# FULL_CB_80_Pin_REV_D.net
KiCad netlist of a schematic drawn in Altium Designer
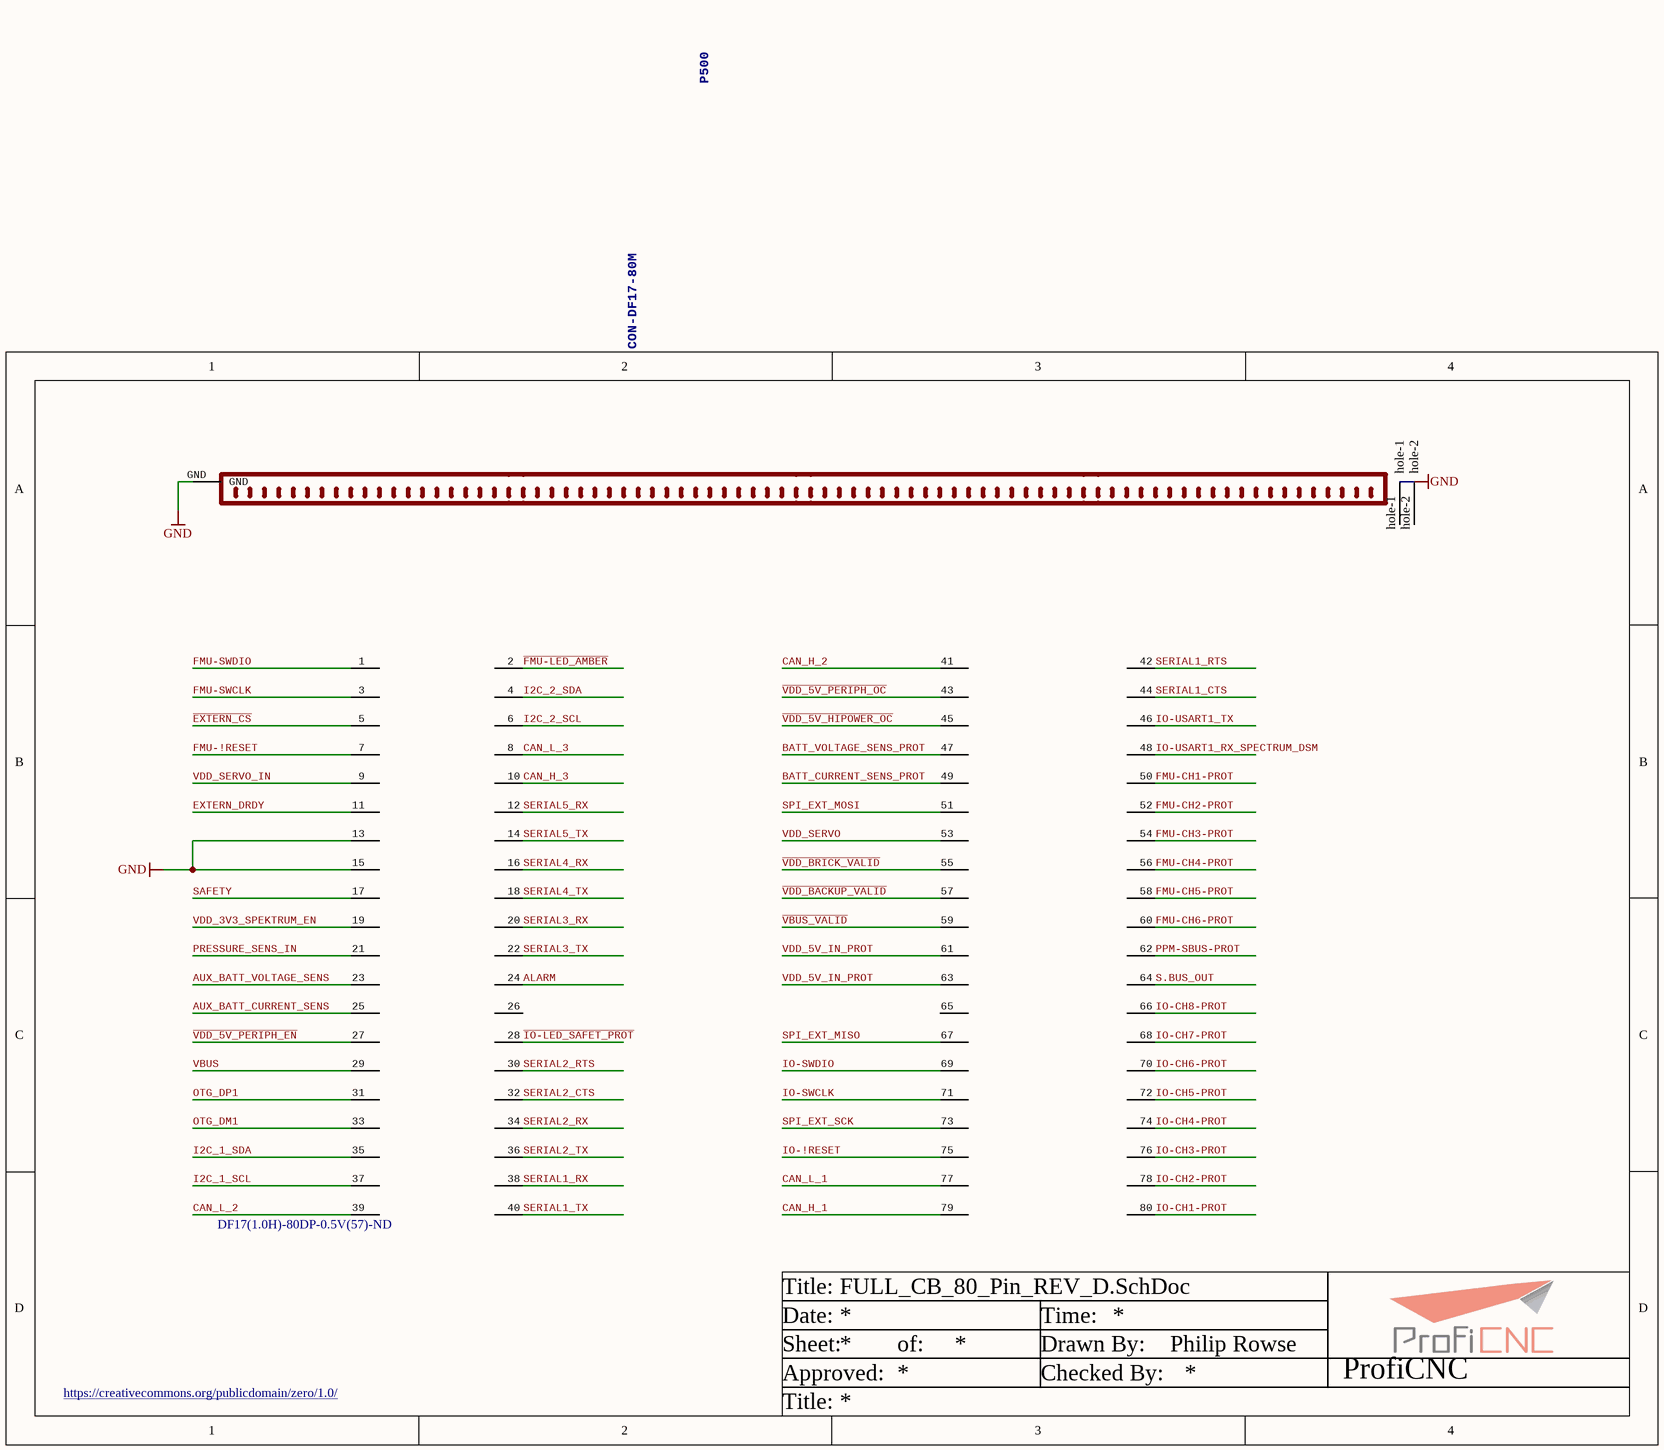
[diagram p0: FULL_CB_80_Pin_REV_D.SchDoc]

(export (version "E")
  (design (tool "Eeschema 10.0.6"))
  (components
    (comp (ref "P500")
      (value "CON-DF17-80M")
      (description "Connector, Header, 80Pos, .5MM, DUAL, SMD, Au")
      (fields (field (name "SUPPLIER PART NUMBER 1") "DF17(1.0H)-80DP-0.5V(57)-ND"))
      (libsource (lib "CB_REV_C") (part "CON-DF17-80M"))
    )
  )
  (nets
    (net (code "1") (name "/ALARM") (class "Default")
      (node (ref "P500") (pin "24") (pinfunction "24_24") (pintype "passive"))
    )
    (net (code "2") (name "/AUX_BATT_CURRENT_SENS") (class "Default")
      (node (ref "P500") (pin "25") (pinfunction "25_25") (pintype "passive"))
    )
    (net (code "3") (name "/AUX_BATT_VOLTAGE_SENS") (class "Default")
      (node (ref "P500") (pin "23") (pinfunction "23_23") (pintype "passive"))
    )
    (net (code "4") (name "/BATT_CURRENT_SENS_PROT") (class "Default")
      (node (ref "P500") (pin "49") (pinfunction "49_49") (pintype "passive"))
    )
    (net (code "5") (name "/BATT_VOLTAGE_SENS_PROT") (class "Default")
      (node (ref "P500") (pin "47") (pinfunction "47_47") (pintype "passive"))
    )
    (net (code "6") (name "/CAN_H_1") (class "Default")
      (node (ref "P500") (pin "79") (pinfunction "79_79") (pintype "passive"))
    )
    (net (code "7") (name "/CAN_H_2") (class "Default")
      (node (ref "P500") (pin "41") (pinfunction "41_41") (pintype "passive"))
    )
    (net (code "8") (name "/CAN_H_3") (class "Default")
      (node (ref "P500") (pin "10") (pinfunction "10_10") (pintype "passive"))
    )
    (net (code "9") (name "/CAN_L_1") (class "Default")
      (node (ref "P500") (pin "77") (pinfunction "77_77") (pintype "passive"))
    )
    (net (code "10") (name "/CAN_L_2") (class "Default")
      (node (ref "P500") (pin "39") (pinfunction "39_39") (pintype "passive"))
    )
    (net (code "11") (name "/CAN_L_3") (class "Default")
      (node (ref "P500") (pin "8") (pinfunction "8_8") (pintype "passive"))
    )
    (net (code "12") (name "/EXTERN_DRDY") (class "Default")
      (node (ref "P500") (pin "11") (pinfunction "11_11") (pintype "passive"))
    )
    (net (code "13") (name "/FMU-!RESET") (class "Default")
      (node (ref "P500") (pin "7") (pinfunction "7_7") (pintype "passive"))
    )
    (net (code "14") (name "/FMU-CH1-PROT") (class "Default")
      (node (ref "P500") (pin "50") (pinfunction "50_50") (pintype "passive"))
    )
    (net (code "15") (name "/FMU-CH2-PROT") (class "Default")
      (node (ref "P500") (pin "52") (pinfunction "52_52") (pintype "passive"))
    )
    (net (code "16") (name "/FMU-CH3-PROT") (class "Default")
      (node (ref "P500") (pin "54") (pinfunction "54_54") (pintype "passive"))
    )
    (net (code "17") (name "/FMU-CH4-PROT") (class "Default")
      (node (ref "P500") (pin "56") (pinfunction "56_56") (pintype "passive"))
    )
    (net (code "18") (name "/FMU-CH5-PROT") (class "Default")
      (node (ref "P500") (pin "58") (pinfunction "58_58") (pintype "passive"))
    )
    (net (code "19") (name "/FMU-CH6-PROT") (class "Default")
      (node (ref "P500") (pin "60") (pinfunction "60_60") (pintype "passive"))
    )
    (net (code "20") (name "/FMU-SWCLK") (class "Default")
      (node (ref "P500") (pin "3") (pinfunction "3_3") (pintype "passive"))
    )
    (net (code "21") (name "/FMU-SWDIO") (class "Default")
      (node (ref "P500") (pin "1") (pinfunction "1_1") (pintype "passive"))
    )
    (net (code "22") (name "/I2C_1_SCL") (class "Default")
      (node (ref "P500") (pin "37") (pinfunction "37_37") (pintype "passive"))
    )
    (net (code "23") (name "/I2C_1_SDA") (class "Default")
      (node (ref "P500") (pin "35") (pinfunction "35_35") (pintype "passive"))
    )
    (net (code "24") (name "/I2C_2_SCL") (class "Default")
      (node (ref "P500") (pin "6") (pinfunction "6_6") (pintype "passive"))
    )
    (net (code "25") (name "/I2C_2_SDA") (class "Default")
      (node (ref "P500") (pin "4") (pinfunction "4_4") (pintype "passive"))
    )
    (net (code "26") (name "/IO-!RESET") (class "Default")
      (node (ref "P500") (pin "75") (pinfunction "75_75") (pintype "passive"))
    )
    (net (code "27") (name "/IO-CH1-PROT") (class "Default")
      (node (ref "P500") (pin "80") (pinfunction "80_80") (pintype "passive"))
    )
    (net (code "28") (name "/IO-CH2-PROT") (class "Default")
      (node (ref "P500") (pin "78") (pinfunction "78_78") (pintype "passive"))
    )
    (net (code "29") (name "/IO-CH3-PROT") (class "Default")
      (node (ref "P500") (pin "76") (pinfunction "76_76") (pintype "passive"))
    )
    (net (code "30") (name "/IO-CH4-PROT") (class "Default")
      (node (ref "P500") (pin "74") (pinfunction "74_74") (pintype "passive"))
    )
    (net (code "31") (name "/IO-CH5-PROT") (class "Default")
      (node (ref "P500") (pin "72") (pinfunction "72_72") (pintype "passive"))
    )
    (net (code "32") (name "/IO-CH6-PROT") (class "Default")
      (node (ref "P500") (pin "70") (pinfunction "70_70") (pintype "passive"))
    )
    (net (code "33") (name "/IO-CH7-PROT") (class "Default")
      (node (ref "P500") (pin "68") (pinfunction "68_68") (pintype "passive"))
    )
    (net (code "34") (name "/IO-CH8-PROT") (class "Default")
      (node (ref "P500") (pin "66") (pinfunction "66_66") (pintype "passive"))
    )
    (net (code "35") (name "/IO-SWCLK") (class "Default")
      (node (ref "P500") (pin "71") (pinfunction "71_71") (pintype "passive"))
    )
    (net (code "36") (name "/IO-SWDIO") (class "Default")
      (node (ref "P500") (pin "69") (pinfunction "69_69") (pintype "passive"))
    )
    (net (code "37") (name "/IO-USART1_RX_SPECTRUM_DSM") (class "Default")
      (node (ref "P500") (pin "48") (pinfunction "48_48") (pintype "passive"))
    )
    (net (code "38") (name "/IO-USART1_TX") (class "Default")
      (node (ref "P500") (pin "46") (pinfunction "46_46") (pintype "passive"))
    )
    (net (code "39") (name "/OTG_DM1") (class "Default")
      (node (ref "P500") (pin "33") (pinfunction "33_33") (pintype "passive"))
    )
    (net (code "40") (name "/OTG_DP1") (class "Default")
      (node (ref "P500") (pin "31") (pinfunction "31_31") (pintype "passive"))
    )
    (net (code "41") (name "/PPM-SBUS-PROT") (class "Default")
      (node (ref "P500") (pin "62") (pinfunction "62_62") (pintype "passive"))
    )
    (net (code "42") (name "/PRESSURE_SENS_IN") (class "Default")
      (node (ref "P500") (pin "21") (pinfunction "21_21") (pintype "passive"))
    )
    (net (code "43") (name "/S.BUS_OUT") (class "Default")
      (node (ref "P500") (pin "64") (pinfunction "64_64") (pintype "passive"))
    )
    (net (code "44") (name "/SAFETY") (class "Default")
      (node (ref "P500") (pin "17") (pinfunction "17_17") (pintype "passive"))
    )
    (net (code "45") (name "/SERIAL1_CTS") (class "Default")
      (node (ref "P500") (pin "44") (pinfunction "44_44") (pintype "passive"))
    )
    (net (code "46") (name "/SERIAL1_RTS") (class "Default")
      (node (ref "P500") (pin "42") (pinfunction "42_42") (pintype "passive"))
    )
    (net (code "47") (name "/SERIAL1_RX") (class "Default")
      (node (ref "P500") (pin "38") (pinfunction "38_38") (pintype "passive"))
    )
    (net (code "48") (name "/SERIAL1_TX") (class "Default")
      (node (ref "P500") (pin "40") (pinfunction "40_40") (pintype "passive"))
    )
    (net (code "49") (name "/SERIAL2_CTS") (class "Default")
      (node (ref "P500") (pin "32") (pinfunction "32_32") (pintype "passive"))
    )
    (net (code "50") (name "/SERIAL2_RTS") (class "Default")
      (node (ref "P500") (pin "30") (pinfunction "30_30") (pintype "passive"))
    )
    (net (code "51") (name "/SERIAL2_RX") (class "Default")
      (node (ref "P500") (pin "34") (pinfunction "34_34") (pintype "passive"))
    )
    (net (code "52") (name "/SERIAL2_TX") (class "Default")
      (node (ref "P500") (pin "36") (pinfunction "36_36") (pintype "passive"))
    )
    (net (code "53") (name "/SERIAL3_RX") (class "Default")
      (node (ref "P500") (pin "20") (pinfunction "20_20") (pintype "passive"))
    )
    (net (code "54") (name "/SERIAL3_TX") (class "Default")
      (node (ref "P500") (pin "22") (pinfunction "22_22") (pintype "passive"))
    )
    (net (code "55") (name "/SERIAL4_RX") (class "Default")
      (node (ref "P500") (pin "16") (pinfunction "16_16") (pintype "passive"))
    )
    (net (code "56") (name "/SERIAL4_TX") (class "Default")
      (node (ref "P500") (pin "18") (pinfunction "18_18") (pintype "passive"))
    )
    (net (code "57") (name "/SERIAL5_RX") (class "Default")
      (node (ref "P500") (pin "12") (pinfunction "12_12") (pintype "passive"))
    )
    (net (code "58") (name "/SERIAL5_TX") (class "Default")
      (node (ref "P500") (pin "14") (pinfunction "14_14") (pintype "passive"))
    )
    (net (code "59") (name "/SPI_EXT_MISO") (class "Default")
      (node (ref "P500") (pin "67") (pinfunction "67_67") (pintype "passive"))
    )
    (net (code "60") (name "/SPI_EXT_MOSI") (class "Default")
      (node (ref "P500") (pin "51") (pinfunction "51_51") (pintype "passive"))
    )
    (net (code "61") (name "/SPI_EXT_SCK") (class "Default")
      (node (ref "P500") (pin "73") (pinfunction "73_73") (pintype "passive"))
    )
    (net (code "62") (name "/VBUS") (class "Default")
      (node (ref "P500") (pin "29") (pinfunction "29_29") (pintype "passive"))
    )
    (net (code "63") (name "/VDD_3V3_SPEKTRUM_EN") (class "Default")
      (node (ref "P500") (pin "19") (pinfunction "19_19") (pintype "passive"))
    )
    (net (code "64") (name "/VDD_5V_IN_PROT") (class "Default")
      (node (ref "P500") (pin "61") (pinfunction "61_61") (pintype "passive"))
      (node (ref "P500") (pin "63") (pinfunction "63_63") (pintype "passive"))
    )
    (net (code "65") (name "/VDD_SERVO") (class "Default")
      (node (ref "P500") (pin "53") (pinfunction "53_53") (pintype "passive"))
    )
    (net (code "66") (name "/VDD_SERVO_IN") (class "Default")
      (node (ref "P500") (pin "9") (pinfunction "9_9") (pintype "passive"))
    )
    (net (code "67") (name "/~{EXTERN_CS}") (class "Default")
      (node (ref "P500") (pin "5") (pinfunction "5_5") (pintype "passive"))
    )
    (net (code "68") (name "/~{FMU-LED_AMBER}") (class "Default")
      (node (ref "P500") (pin "2") (pinfunction "2_2") (pintype "passive"))
    )
    (net (code "69") (name "/~{IO-LED_SAFET_PROT}") (class "Default")
      (node (ref "P500") (pin "28") (pinfunction "28_28") (pintype "passive"))
    )
    (net (code "70") (name "/~{VBUS_VALID}") (class "Default")
      (node (ref "P500") (pin "59") (pinfunction "59_59") (pintype "passive"))
    )
    (net (code "71") (name "/~{VDD_5V_HIPOWER_OC}") (class "Default")
      (node (ref "P500") (pin "45") (pinfunction "45_45") (pintype "passive"))
    )
    (net (code "72") (name "/~{VDD_5V_PERIPH_EN}") (class "Default")
      (node (ref "P500") (pin "27") (pinfunction "27_27") (pintype "passive"))
    )
    (net (code "73") (name "/~{VDD_5V_PERIPH_OC}") (class "Default")
      (node (ref "P500") (pin "43") (pinfunction "43_43") (pintype "passive"))
    )
    (net (code "74") (name "/~{VDD_BACKUP_VALID}") (class "Default")
      (node (ref "P500") (pin "57") (pinfunction "57_57") (pintype "passive"))
    )
    (net (code "75") (name "/~{VDD_BRICK_VALID}") (class "Default")
      (node (ref "P500") (pin "55") (pinfunction "55_55") (pintype "passive"))
    )
    (net (code "76") (name "GND") (class "Default")
      (node (ref "P500") (pin "13") (pinfunction "13_13") (pintype "passive"))
      (node (ref "P500") (pin "15") (pinfunction "15_15") (pintype "passive"))
      (node (ref "P500") (pin "GND") (pinfunction "GND_GND") (pintype "passive"))
    )
    (net (code "77") (name "unconnected-(P500-Pad26)") (class "Default")
      (node (ref "P500") (pin "26") (pinfunction "26_26") (pintype "passive"))
    )
    (net (code "78") (name "unconnected-(P500-Pad65)") (class "Default")
      (node (ref "P500") (pin "65") (pinfunction "65_65") (pintype "passive"))
    )
    (net (code "79") (name "unconnected-(P500-Padhole-1)") (class "Default")
      (node (ref "P500") (pin "hole-1") (pinfunction "hole-1_hole-1") (pintype "passive"))
    )
    (net (code "80") (name "unconnected-(P500-Padhole-2)") (class "Default")
      (node (ref "P500") (pin "hole-2") (pinfunction "hole-2_hole-2") (pintype "passive"))
    )
  )
)
